# GL850G.net
KiCad netlist of a schematic drawn in Altium Designer
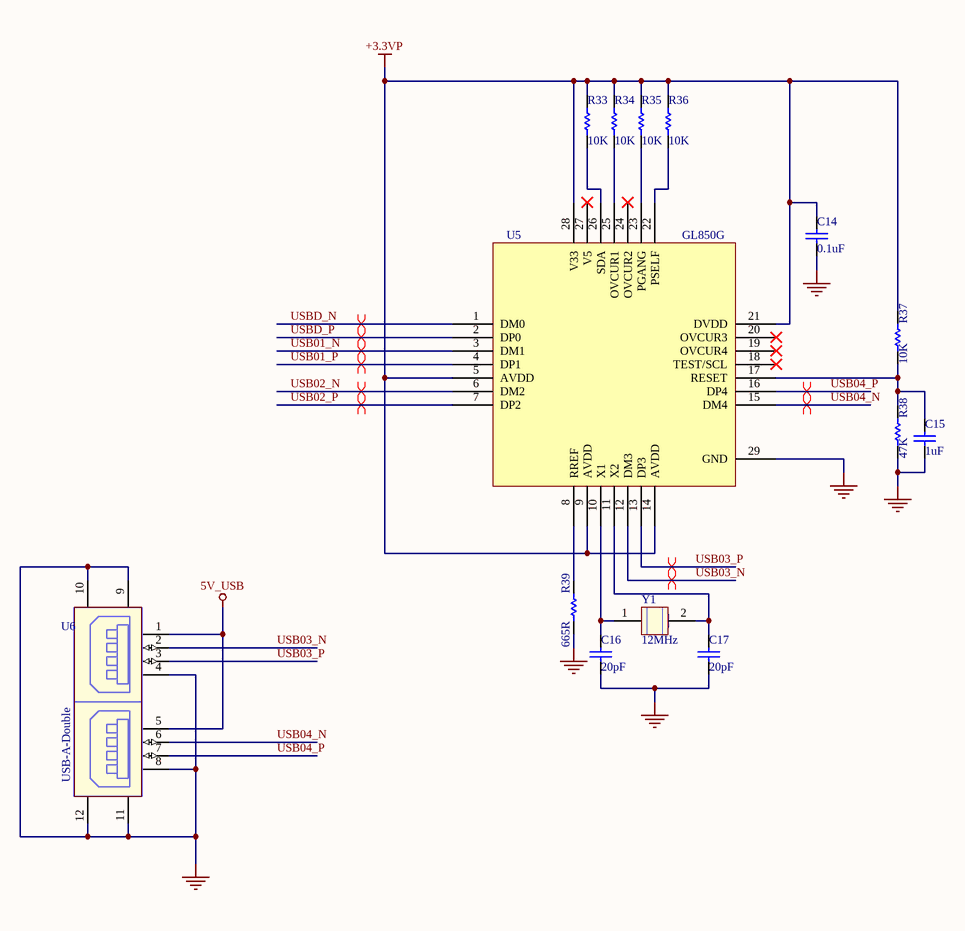
[diagram p0: GL850G.SchDoc]

(export (version "E")
  (design (tool "Eeschema 10.0.6"))
  (components
    (comp (ref "C14")
      (value "0.1uF")
      (footprint "C0603L")
      (description "Capacitor (Semiconductor SIM Model)")
      (fields (field (name "Comment") "Cap Semi") (field (name "PUBLISHER") "Altium Limited"))
      (libsource (lib "Miscellaneous Devices") (part "Cap Semi"))
    )
    (comp (ref "C15")
      (value "1uF")
      (footprint "C0603L")
      (description "Capacitor (Semiconductor SIM Model)")
      (fields (field (name "Comment") "Cap Semi") (field (name "PUBLISHER") "Altium Limited"))
      (libsource (lib "Miscellaneous Devices") (part "Cap Semi"))
    )
    (comp (ref "C16")
      (value "20pF")
      (footprint "C0603L")
      (description "Capacitor (Semiconductor SIM Model)")
      (fields (field (name "Comment") "Cap Semi") (field (name "PUBLISHER") "Altium Limited"))
      (libsource (lib "Miscellaneous Devices") (part "Cap Semi"))
    )
    (comp (ref "C17")
      (value "20pF")
      (footprint "C0603L")
      (description "Capacitor (Semiconductor SIM Model)")
      (fields (field (name "Comment") "Cap Semi") (field (name "PUBLISHER") "Altium Limited"))
      (libsource (lib "Miscellaneous Devices") (part "Cap Semi"))
    )
    (comp (ref "R33")
      (value "10K")
      (footprint "R0603L")
      (description "Semiconductor Resistor")
      (fields (field (name "Comment") "Res Semi") (field (name "PUBLISHER") "Altium Limited"))
      (libsource (lib "Miscellaneous Devices") (part "Res Semi"))
    )
    (comp (ref "R34")
      (value "10K")
      (footprint "R0603L")
      (description "Semiconductor Resistor")
      (fields (field (name "Comment") "Res Semi") (field (name "PUBLISHER") "Altium Limited"))
      (libsource (lib "Miscellaneous Devices") (part "Res Semi"))
    )
    (comp (ref "R35")
      (value "10K")
      (footprint "R0603L")
      (description "Semiconductor Resistor")
      (fields (field (name "Comment") "Res Semi") (field (name "PUBLISHER") "Altium Limited"))
      (libsource (lib "Miscellaneous Devices") (part "Res Semi"))
    )
    (comp (ref "R36")
      (value "10K")
      (footprint "R0603L")
      (description "Semiconductor Resistor")
      (fields (field (name "Comment") "Res Semi") (field (name "PUBLISHER") "Altium Limited"))
      (libsource (lib "Miscellaneous Devices") (part "Res Semi"))
    )
    (comp (ref "R37")
      (value "10K")
      (footprint "R0603L")
      (description "Semiconductor Resistor")
      (fields (field (name "Comment") "Res Semi") (field (name "PUBLISHER") "Altium Limited"))
      (libsource (lib "Miscellaneous Devices") (part "Res Semi"))
    )
    (comp (ref "R38")
      (value "47K")
      (footprint "R0603L")
      (description "Semiconductor Resistor")
      (fields (field (name "Comment") "Res Semi") (field (name "PUBLISHER") "Altium Limited"))
      (libsource (lib "Miscellaneous Devices") (part "Res Semi"))
    )
    (comp (ref "R39")
      (value "665R")
      (footprint "R0603L")
      (description "Semiconductor Resistor")
      (fields (field (name "Comment") "Res Semi") (field (name "PUBLISHER") "Altium Limited"))
      (libsource (lib "Miscellaneous Devices") (part "Res Semi"))
    )
    (comp (ref "U5")
      (value "GL850G")
      (footprint "GL850G-QFN28")
      (libsource (lib "wooya_lib_footprint") (part "GL850G"))
    )
    (comp (ref "U6")
      (value "USB-A-Double")
      (footprint "USB-DB")
      (libsource (lib "WOOYA_LIB_FOOTPRINT") (part "USB-A-Double"))
    )
    (comp (ref "Y1")
      (value "12MHz")
      (footprint "XTAL1")
      (fields (field (name "Comment") "Oscillator"))
      (libsource (lib "WOOYA_LIB_FOOTPRINT") (part "Oscillator"))
    )
  )
  (nets
    (net (code "1") (name "+3.3VP") (class "Default")
      (node (ref "C14") (pin "1") (pinfunction "1_1") (pintype "passive"))
      (node (ref "R33") (pin "2") (pinfunction "2_2") (pintype "passive"))
      (node (ref "R34") (pin "2") (pinfunction "2_2") (pintype "passive"))
      (node (ref "R35") (pin "2") (pinfunction "2_2") (pintype "passive"))
      (node (ref "R36") (pin "2") (pinfunction "2_2") (pintype "passive"))
      (node (ref "R37") (pin "2") (pinfunction "2_2") (pintype "passive"))
      (node (ref "U5") (pin "14") (pinfunction "AVDD_14") (pintype "passive"))
      (node (ref "U5") (pin "21") (pinfunction "DVDD_21") (pintype "passive"))
      (node (ref "U5") (pin "28") (pinfunction "V33_28") (pintype "passive"))
      (node (ref "U5") (pin "5") (pinfunction "AVDD_5") (pintype "passive"))
      (node (ref "U5") (pin "9") (pinfunction "AVDD_9") (pintype "passive"))
    )
    (net (code "2") (name "/USB01_N") (class "Default")
      (node (ref "U5") (pin "3") (pinfunction "DM1_3") (pintype "passive"))
    )
    (net (code "3") (name "/USB01_P") (class "Default")
      (node (ref "U5") (pin "4") (pinfunction "DP1_4") (pintype "passive"))
    )
    (net (code "4") (name "/USB02_N") (class "Default")
      (node (ref "U5") (pin "6") (pinfunction "DM2_6") (pintype "passive"))
    )
    (net (code "5") (name "/USB02_P") (class "Default")
      (node (ref "U5") (pin "7") (pinfunction "DP2_7") (pintype "passive"))
    )
    (net (code "6") (name "/USB03_N") (class "Default")
      (node (ref "U5") (pin "12") (pinfunction "DM3_12") (pintype "passive"))
      (node (ref "U6") (pin "2") (pinfunction "D-_2") (pintype "bidirectional"))
    )
    (net (code "7") (name "/USB03_P") (class "Default")
      (node (ref "U5") (pin "13") (pinfunction "DP3_13") (pintype "passive"))
      (node (ref "U6") (pin "3") (pinfunction "D+_3") (pintype "bidirectional"))
    )
    (net (code "8") (name "/USB04_N") (class "Default")
      (node (ref "U5") (pin "15") (pinfunction "DM4_15") (pintype "passive"))
      (node (ref "U6") (pin "6") (pinfunction "NC_6") (pintype "bidirectional"))
    )
    (net (code "9") (name "/USB04_P") (class "Default")
      (node (ref "U5") (pin "16") (pinfunction "DP4_16") (pintype "passive"))
      (node (ref "U6") (pin "7") (pinfunction "NC_7") (pintype "bidirectional"))
    )
    (net (code "10") (name "/USBD_N") (class "Default")
      (node (ref "U5") (pin "1") (pinfunction "DM0_1") (pintype "passive"))
    )
    (net (code "11") (name "/USBD_P") (class "Default")
      (node (ref "U5") (pin "2") (pinfunction "DP0_2") (pintype "passive"))
    )
    (net (code "12") (name "5V_USB") (class "Default")
      (node (ref "U6") (pin "1") (pinfunction "V+_1") (pintype "passive"))
      (node (ref "U6") (pin "5") (pinfunction "NC_5") (pintype "passive"))
    )
    (net (code "13") (name "GND") (class "Default")
      (node (ref "C14") (pin "2") (pinfunction "2_2") (pintype "passive"))
      (node (ref "C15") (pin "2") (pinfunction "2_2") (pintype "passive"))
      (node (ref "C16") (pin "2") (pinfunction "2_2") (pintype "passive"))
      (node (ref "C17") (pin "2") (pinfunction "2_2") (pintype "passive"))
      (node (ref "R38") (pin "1") (pinfunction "1_1") (pintype "passive"))
      (node (ref "R39") (pin "1") (pinfunction "1_1") (pintype "passive"))
      (node (ref "U5") (pin "29") (pinfunction "GND_29") (pintype "passive"))
      (node (ref "U6") (pin "10") (pinfunction "10_10") (pintype "passive"))
      (node (ref "U6") (pin "11") (pinfunction "11_11") (pintype "passive"))
      (node (ref "U6") (pin "12") (pinfunction "12_12") (pintype "passive"))
      (node (ref "U6") (pin "4") (pinfunction "G_4") (pintype "passive"))
      (node (ref "U6") (pin "8") (pinfunction "NC_8") (pintype "passive"))
      (node (ref "U6") (pin "9") (pinfunction "9_9") (pintype "passive"))
    )
    (net (code "14") (name "Net-(U5-OVCUR1)") (class "Default")
      (node (ref "R34") (pin "1") (pinfunction "1_1") (pintype "passive"))
      (node (ref "U5") (pin "25") (pinfunction "OVCUR1_25") (pintype "passive"))
    )
    (net (code "15") (name "Net-(U5-PGANG)") (class "Default")
      (node (ref "R35") (pin "1") (pinfunction "1_1") (pintype "passive"))
      (node (ref "U5") (pin "23") (pinfunction "PGANG_23") (pintype "passive"))
    )
    (net (code "16") (name "Net-(U5-PSELF)") (class "Default")
      (node (ref "R36") (pin "1") (pinfunction "1_1") (pintype "passive"))
      (node (ref "U5") (pin "22") (pinfunction "PSELF_22") (pintype "passive"))
    )
    (net (code "17") (name "Net-(U5-RESET)") (class "Default")
      (node (ref "C15") (pin "1") (pinfunction "1_1") (pintype "passive"))
      (node (ref "R37") (pin "1") (pinfunction "1_1") (pintype "passive"))
      (node (ref "R38") (pin "2") (pinfunction "2_2") (pintype "passive"))
      (node (ref "U5") (pin "17") (pinfunction "RESET_17") (pintype "passive"))
    )
    (net (code "18") (name "Net-(U5-RREF)") (class "Default")
      (node (ref "R39") (pin "2") (pinfunction "2_2") (pintype "passive"))
      (node (ref "U5") (pin "8") (pinfunction "RREF_8") (pintype "passive"))
    )
    (net (code "19") (name "Net-(U5-SDA)") (class "Default")
      (node (ref "R33") (pin "1") (pinfunction "1_1") (pintype "passive"))
      (node (ref "U5") (pin "26") (pinfunction "SDA_26") (pintype "passive"))
    )
    (net (code "20") (name "Net-(U5-X1)") (class "Default")
      (node (ref "C16") (pin "1") (pinfunction "1_1") (pintype "passive"))
      (node (ref "U5") (pin "10") (pinfunction "X1_10") (pintype "passive"))
      (node (ref "Y1") (pin "1") (pinfunction "1_1") (pintype "passive"))
    )
    (net (code "21") (name "Net-(U5-X2)") (class "Default")
      (node (ref "C17") (pin "1") (pinfunction "1_1") (pintype "passive"))
      (node (ref "U5") (pin "11") (pinfunction "X2_11") (pintype "passive"))
      (node (ref "Y1") (pin "2") (pinfunction "2_2") (pintype "passive"))
    )
    (net (code "22") (name "unconnected-(U5-OVCUR2-Pad24)") (class "Default")
      (node (ref "U5") (pin "24") (pinfunction "OVCUR2_24") (pintype "passive+no_connect"))
    )
    (net (code "23") (name "unconnected-(U5-OVCUR3-Pad20)") (class "Default")
      (node (ref "U5") (pin "20") (pinfunction "OVCUR3_20") (pintype "passive+no_connect"))
    )
    (net (code "24") (name "unconnected-(U5-OVCUR4-Pad19)") (class "Default")
      (node (ref "U5") (pin "19") (pinfunction "OVCUR4_19") (pintype "passive+no_connect"))
    )
    (net (code "25") (name "unconnected-(U5-TEST{slash}SCL-Pad18)") (class "Default")
      (node (ref "U5") (pin "18") (pinfunction "TEST/SCL_18") (pintype "passive+no_connect"))
    )
    (net (code "26") (name "unconnected-(U5-V5-Pad27)") (class "Default")
      (node (ref "U5") (pin "27") (pinfunction "V5_27") (pintype "passive+no_connect"))
    )
  )
)
